# 2LD-20-mk-1_1_0.net
KiCad netlist of a schematic drawn in EAGLE
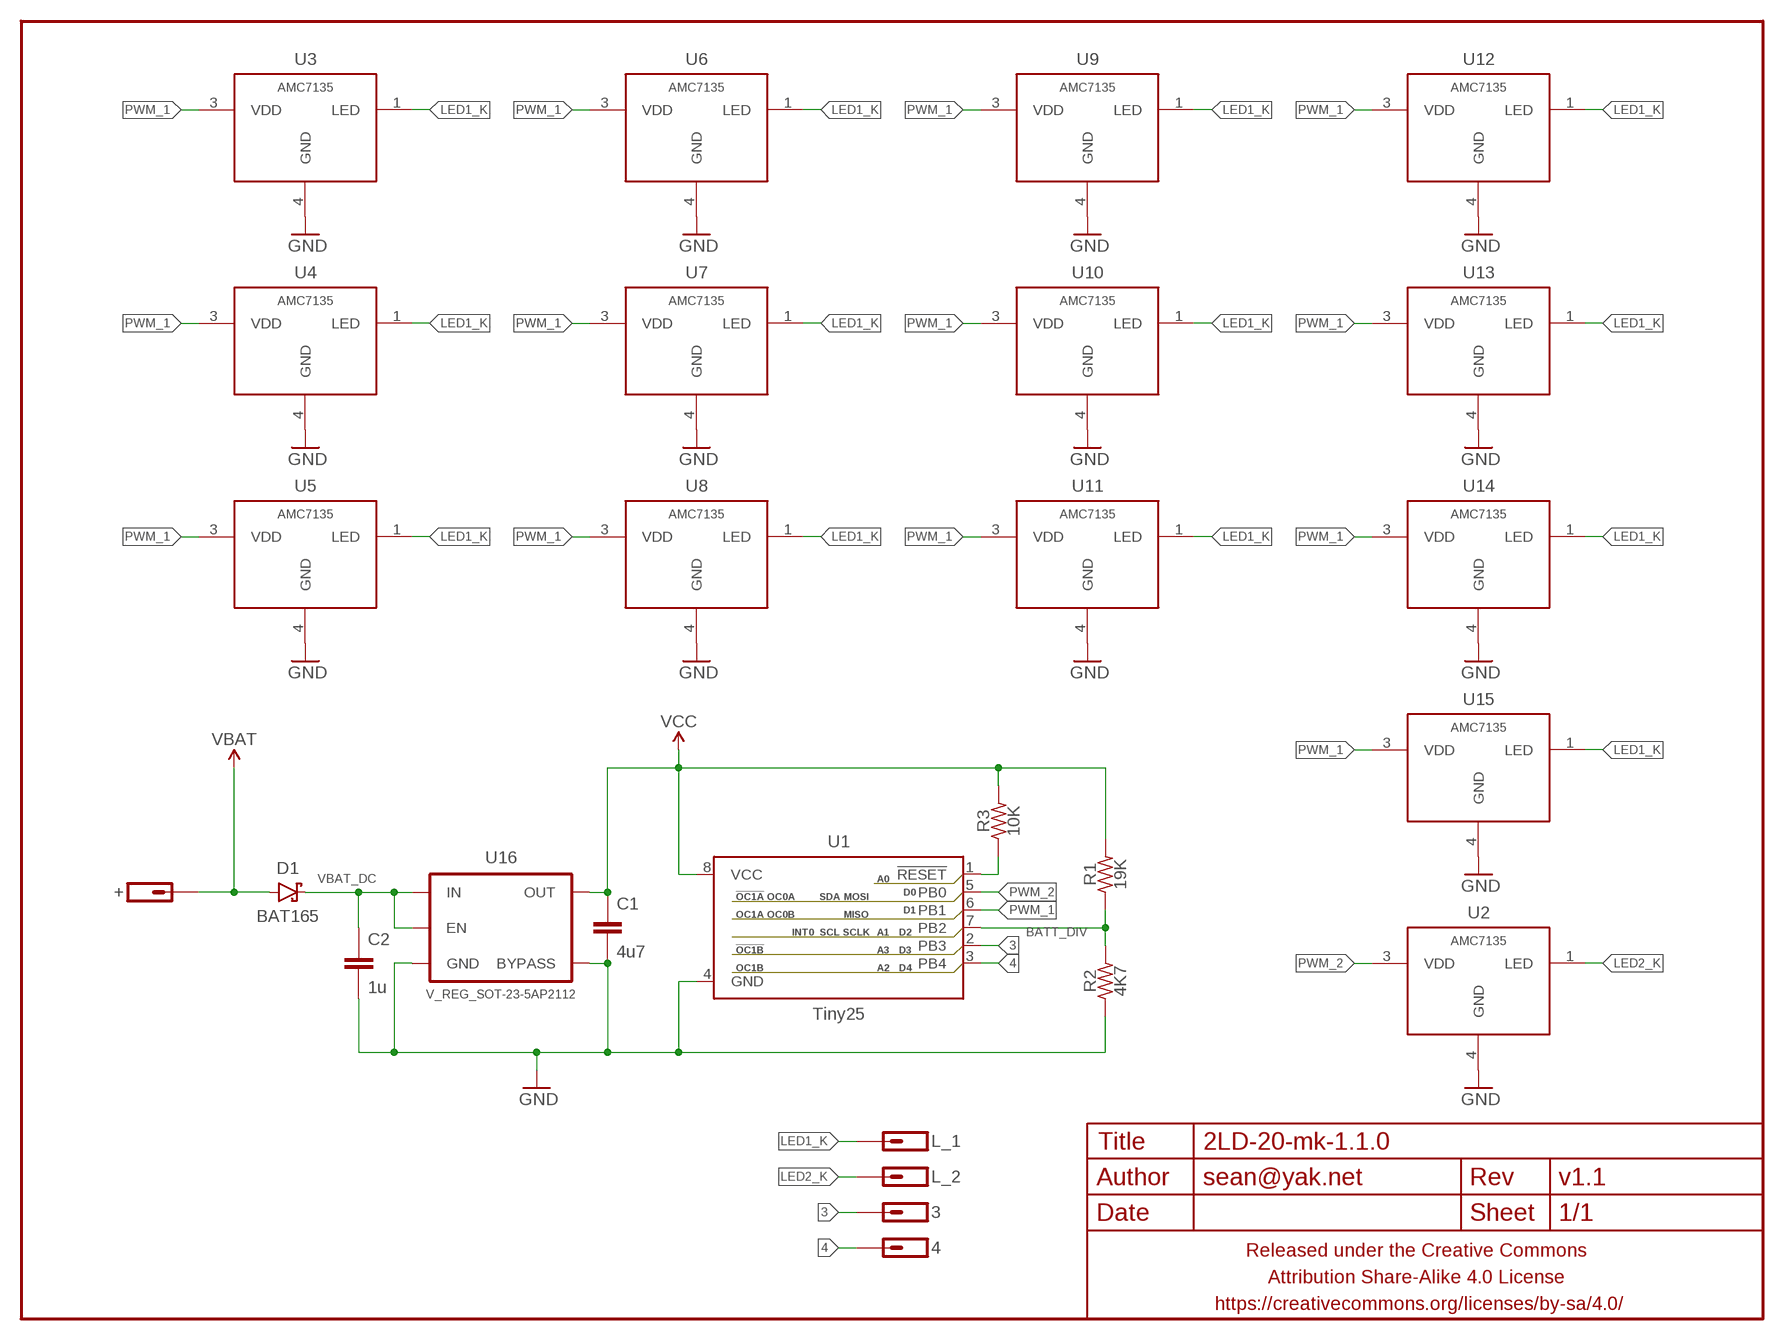
[diagram p0: schematic, sheet 1]

(export (version "E")
  (design (tool "Eeschema 10.0.6"))
  (components
    (comp (ref "+")
      (value "M01PTH-1MM-CIR-NS")
      (footprint "eagle-import:1X01-1MM-CIR-NS")
      (libsource (lib "eagle-import") (part "M01PTH-1MM-CIR-NS"))
    )
    (comp (ref "3")
      (value "M01SMD-1MM-DIA-NS")
      (footprint "eagle-import:1X01-SMD-1MM-DIA-NS")
      (libsource (lib "eagle-import") (part "M01SMD-1MM-DIA-NS"))
    )
    (comp (ref "4")
      (value "M01SMD-1MM-DIA-NS")
      (footprint "eagle-import:1X01-SMD-1MM-DIA-NS")
      (libsource (lib "eagle-import") (part "M01SMD-1MM-DIA-NS"))
    )
    (comp (ref "C1")
      (value "4u7")
      (footprint "eagle-import:C0603-TIGHTER")
      (libsource (lib "eagle-import") (part "CAPACITOR-CERAMICC0603-TIGHTER"))
    )
    (comp (ref "C2")
      (value "1u")
      (footprint "eagle-import:C0402")
      (libsource (lib "eagle-import") (part "CAPACITOR-CERAMICC0402"))
    )
    (comp (ref "D1")
      (value "BAT165")
      (footprint "eagle-import:SOD323-SCHOTTKY")
      (libsource (lib "eagle-import") (part "DIODE-SCHOTTKYSOD323"))
    )
    (comp (ref "FRAME1")
      (value "FRAME-LETTERNO_PACKAGE")
      (footprint "eagle-import:DUMMY")
      (fields (field (name "DESIGNER") "sean@yak.net") (field (name "VERSION") "v1.1"))
      (libsource (lib "eagle-import") (part "FRAME-LETTERNO_PACKAGE"))
    )
    (comp (ref "L_1")
      (value "M011X01-0.9MM-CIR")
      (footprint "eagle-import:1X01-0.9MM-CIR")
      (libsource (lib "eagle-import") (part "M011X01-0.9MM-CIR"))
    )
    (comp (ref "L_2")
      (value "M01PTH-0.8MM-CIR")
      (footprint "eagle-import:1X01-0.8MM-CIR")
      (libsource (lib "eagle-import") (part "M01PTH-0.8MM-CIR"))
    )
    (comp (ref "R1")
      (value "19K")
      (footprint "eagle-import:R0402")
      (libsource (lib "eagle-import") (part "RESISTORR0402"))
    )
    (comp (ref "R2")
      (value "4K7")
      (footprint "eagle-import:R0402")
      (libsource (lib "eagle-import") (part "RESISTORR0402"))
    )
    (comp (ref "R3")
      (value "10K")
      (footprint "eagle-import:R0402")
      (libsource (lib "eagle-import") (part "RESISTORR0402"))
    )
    (comp (ref "U1")
      (value "Tiny25")
      (footprint "eagle-import:SO08-NARROWER")
      (libsource (lib "eagle-import") (part "ATTINY13SOIC-NARROWPADS"))
    )
    (comp (ref "U2")
      (value "AMC7135")
      (footprint "eagle-import:SOT89-NOTHERM-ROUNDED-LESS")
      (libsource (lib "eagle-import") (part "AMC7135SOT-89-NOTHERM-ROUNDED-LESS"))
    )
    (comp (ref "U3")
      (value "AMC7135")
      (footprint "eagle-import:SOT89-NOTHERM-ROUNDED-LESS")
      (libsource (lib "eagle-import") (part "AMC7135SOT-89-NOTHERM-ROUNDED-LESS"))
    )
    (comp (ref "U4")
      (value "AMC7135")
      (footprint "eagle-import:SOT89-NOTHERM-ROUNDED-LESS")
      (libsource (lib "eagle-import") (part "AMC7135SOT-89-NOTHERM-ROUNDED-LESS"))
    )
    (comp (ref "U5")
      (value "AMC7135")
      (footprint "eagle-import:SOT89-NOTHERM-ROUNDED-LESS")
      (libsource (lib "eagle-import") (part "AMC7135SOT-89-NOTHERM-ROUNDED-LESS"))
    )
    (comp (ref "U6")
      (value "AMC7135")
      (footprint "eagle-import:SOT89-NOTHERM-ROUNDED-LESS")
      (libsource (lib "eagle-import") (part "AMC7135SOT-89-NOTHERM-ROUNDED-LESS"))
    )
    (comp (ref "U7")
      (value "AMC7135")
      (footprint "eagle-import:SOT89-NOTHERM-ROUNDED-LESS")
      (libsource (lib "eagle-import") (part "AMC7135SOT-89-NOTHERM-ROUNDED-LESS"))
    )
    (comp (ref "U8")
      (value "AMC7135")
      (footprint "eagle-import:SOT89-NOTHERM-ROUNDED-LESS")
      (libsource (lib "eagle-import") (part "AMC7135SOT-89-NOTHERM-ROUNDED-LESS"))
    )
    (comp (ref "U9")
      (value "AMC7135")
      (footprint "eagle-import:SOT89-NOTHERM-ROUNDED-LESS")
      (libsource (lib "eagle-import") (part "AMC7135SOT-89-NOTHERM-ROUNDED-LESS"))
    )
    (comp (ref "U10")
      (value "AMC7135")
      (footprint "eagle-import:SOT89-NOTHERM-ROUNDED-LESS")
      (libsource (lib "eagle-import") (part "AMC7135SOT-89-NOTHERM-ROUNDED-LESS"))
    )
    (comp (ref "U11")
      (value "AMC7135")
      (footprint "eagle-import:SOT89-NOTHERM-ROUNDED-LESS")
      (libsource (lib "eagle-import") (part "AMC7135SOT-89-NOTHERM-ROUNDED-LESS"))
    )
    (comp (ref "U12")
      (value "AMC7135")
      (footprint "eagle-import:SOT89-NOTHERM-ROUNDED-LESS")
      (libsource (lib "eagle-import") (part "AMC7135SOT-89-NOTHERM-ROUNDED-LESS"))
    )
    (comp (ref "U13")
      (value "AMC7135")
      (footprint "eagle-import:SOT89-NOTHERM-ROUNDED-LESS")
      (libsource (lib "eagle-import") (part "AMC7135SOT-89-NOTHERM-ROUNDED-LESS"))
    )
    (comp (ref "U14")
      (value "AMC7135")
      (footprint "eagle-import:SOT89-NOTHERM-ROUNDED-LESS")
      (libsource (lib "eagle-import") (part "AMC7135SOT-89-NOTHERM-ROUNDED-LESS"))
    )
    (comp (ref "U15")
      (value "AMC7135")
      (footprint "eagle-import:SOT89-NOTHERM-ROUNDED-LESS")
      (libsource (lib "eagle-import") (part "AMC7135SOT-89-NOTHERM-ROUNDED-LESS"))
    )
    (comp (ref "U16")
      (value "V_REG_SOT-23-5AP2112")
      (footprint "eagle-import:SOT23-5")
      (libsource (lib "eagle-import") (part "V_REG_SOT-23-5AP2112"))
    )
  )
  (nets
    (net (code "1") (name "/BATT_DIV") (class "Default")
      (node (ref "R1") (pin "1") (pinfunction "1_1") (pintype "passive"))
      (node (ref "R2") (pin "2") (pinfunction "2_2") (pintype "passive"))
      (node (ref "U1") (pin "7") (pinfunction "PB2_7") (pintype "bidirectional"))
    )
    (net (code "2") (name "/VBAT_DC") (class "Default")
      (node (ref "C2") (pin "1") (pinfunction "1_1") (pintype "passive"))
      (node (ref "D1") (pin "C") (pinfunction "C_C") (pintype "passive"))
      (node (ref "U16") (pin "1") (pinfunction "IN_1") (pintype "input"))
      (node (ref "U16") (pin "3") (pinfunction "EN_3") (pintype "input"))
    )
    (net (code "3") (name "3") (class "Default")
      (node (ref "3") (pin "P$1") (pinfunction "1_P$1") (pintype "passive"))
      (node (ref "U1") (pin "2") (pinfunction "PB3_2") (pintype "bidirectional"))
    )
    (net (code "4") (name "4") (class "Default")
      (node (ref "4") (pin "P$1") (pinfunction "1_P$1") (pintype "passive"))
      (node (ref "U1") (pin "3") (pinfunction "PB4_3") (pintype "bidirectional"))
    )
    (net (code "5") (name "GND") (class "Default")
      (node (ref "C1") (pin "2") (pinfunction "2_2") (pintype "passive"))
      (node (ref "C2") (pin "2") (pinfunction "2_2") (pintype "passive"))
      (node (ref "R2") (pin "1") (pinfunction "1_1") (pintype "passive"))
      (node (ref "U1") (pin "4") (pinfunction "GND_4") (pintype "bidirectional"))
      (node (ref "U10") (pin "4") (pinfunction "GND_4") (pintype "bidirectional"))
      (node (ref "U11") (pin "4") (pinfunction "GND_4") (pintype "bidirectional"))
      (node (ref "U12") (pin "4") (pinfunction "GND_4") (pintype "bidirectional"))
      (node (ref "U13") (pin "4") (pinfunction "GND_4") (pintype "bidirectional"))
      (node (ref "U14") (pin "4") (pinfunction "GND_4") (pintype "bidirectional"))
      (node (ref "U15") (pin "4") (pinfunction "GND_4") (pintype "bidirectional"))
      (node (ref "U16") (pin "2") (pinfunction "GND_2") (pintype "input"))
      (node (ref "U16") (pin "4") (pinfunction "BYPASS_4") (pintype "input"))
      (node (ref "U2") (pin "4") (pinfunction "GND_4") (pintype "bidirectional"))
      (node (ref "U3") (pin "4") (pinfunction "GND_4") (pintype "bidirectional"))
      (node (ref "U4") (pin "4") (pinfunction "GND_4") (pintype "bidirectional"))
      (node (ref "U5") (pin "4") (pinfunction "GND_4") (pintype "bidirectional"))
      (node (ref "U6") (pin "4") (pinfunction "GND_4") (pintype "bidirectional"))
      (node (ref "U7") (pin "4") (pinfunction "GND_4") (pintype "bidirectional"))
      (node (ref "U8") (pin "4") (pinfunction "GND_4") (pintype "bidirectional"))
      (node (ref "U9") (pin "4") (pinfunction "GND_4") (pintype "bidirectional"))
    )
    (net (code "6") (name "LED1_K") (class "Default")
      (node (ref "L_1") (pin "P$1") (pinfunction "1_P$1") (pintype "passive"))
      (node (ref "U10") (pin "1") (pinfunction "LED_1") (pintype "bidirectional"))
      (node (ref "U11") (pin "1") (pinfunction "LED_1") (pintype "bidirectional"))
      (node (ref "U12") (pin "1") (pinfunction "LED_1") (pintype "bidirectional"))
      (node (ref "U13") (pin "1") (pinfunction "LED_1") (pintype "bidirectional"))
      (node (ref "U14") (pin "1") (pinfunction "LED_1") (pintype "bidirectional"))
      (node (ref "U15") (pin "1") (pinfunction "LED_1") (pintype "bidirectional"))
      (node (ref "U3") (pin "1") (pinfunction "LED_1") (pintype "bidirectional"))
      (node (ref "U4") (pin "1") (pinfunction "LED_1") (pintype "bidirectional"))
      (node (ref "U5") (pin "1") (pinfunction "LED_1") (pintype "bidirectional"))
      (node (ref "U6") (pin "1") (pinfunction "LED_1") (pintype "bidirectional"))
      (node (ref "U7") (pin "1") (pinfunction "LED_1") (pintype "bidirectional"))
      (node (ref "U8") (pin "1") (pinfunction "LED_1") (pintype "bidirectional"))
      (node (ref "U9") (pin "1") (pinfunction "LED_1") (pintype "bidirectional"))
    )
    (net (code "7") (name "LED2_K") (class "Default")
      (node (ref "L_2") (pin "1") (pinfunction "1_1") (pintype "passive"))
      (node (ref "U2") (pin "1") (pinfunction "LED_1") (pintype "bidirectional"))
    )
    (net (code "8") (name "Net-(U1-~{RESET})") (class "Default")
      (node (ref "R3") (pin "1") (pinfunction "1_1") (pintype "passive"))
      (node (ref "U1") (pin "1") (pinfunction "~{RESET}_1") (pintype "bidirectional"))
    )
    (net (code "9") (name "PWM_1") (class "Default")
      (node (ref "U1") (pin "6") (pinfunction "PB1_6") (pintype "bidirectional"))
      (node (ref "U10") (pin "3") (pinfunction "VDD_3") (pintype "bidirectional"))
      (node (ref "U11") (pin "3") (pinfunction "VDD_3") (pintype "bidirectional"))
      (node (ref "U12") (pin "3") (pinfunction "VDD_3") (pintype "bidirectional"))
      (node (ref "U13") (pin "3") (pinfunction "VDD_3") (pintype "bidirectional"))
      (node (ref "U14") (pin "3") (pinfunction "VDD_3") (pintype "bidirectional"))
      (node (ref "U15") (pin "3") (pinfunction "VDD_3") (pintype "bidirectional"))
      (node (ref "U3") (pin "3") (pinfunction "VDD_3") (pintype "bidirectional"))
      (node (ref "U4") (pin "3") (pinfunction "VDD_3") (pintype "bidirectional"))
      (node (ref "U5") (pin "3") (pinfunction "VDD_3") (pintype "bidirectional"))
      (node (ref "U6") (pin "3") (pinfunction "VDD_3") (pintype "bidirectional"))
      (node (ref "U7") (pin "3") (pinfunction "VDD_3") (pintype "bidirectional"))
      (node (ref "U8") (pin "3") (pinfunction "VDD_3") (pintype "bidirectional"))
      (node (ref "U9") (pin "3") (pinfunction "VDD_3") (pintype "bidirectional"))
    )
    (net (code "10") (name "PWM_2") (class "Default")
      (node (ref "U1") (pin "5") (pinfunction "PB0_5") (pintype "bidirectional"))
      (node (ref "U2") (pin "3") (pinfunction "VDD_3") (pintype "bidirectional"))
    )
    (net (code "11") (name "VBAT") (class "Default")
      (node (ref "+") (pin "1") (pinfunction "1_1") (pintype "passive"))
      (node (ref "D1") (pin "A") (pinfunction "A_A") (pintype "passive"))
    )
    (net (code "12") (name "VCC") (class "Default")
      (node (ref "C1") (pin "1") (pinfunction "1_1") (pintype "passive"))
      (node (ref "R1") (pin "2") (pinfunction "2_2") (pintype "passive"))
      (node (ref "R3") (pin "2") (pinfunction "2_2") (pintype "passive"))
      (node (ref "U1") (pin "8") (pinfunction "VCC_8") (pintype "bidirectional"))
      (node (ref "U16") (pin "5") (pinfunction "OUT_5") (pintype "passive"))
    )
  )
)
